# untitled.net
KiCad netlist of a schematic drawn in EAGLE
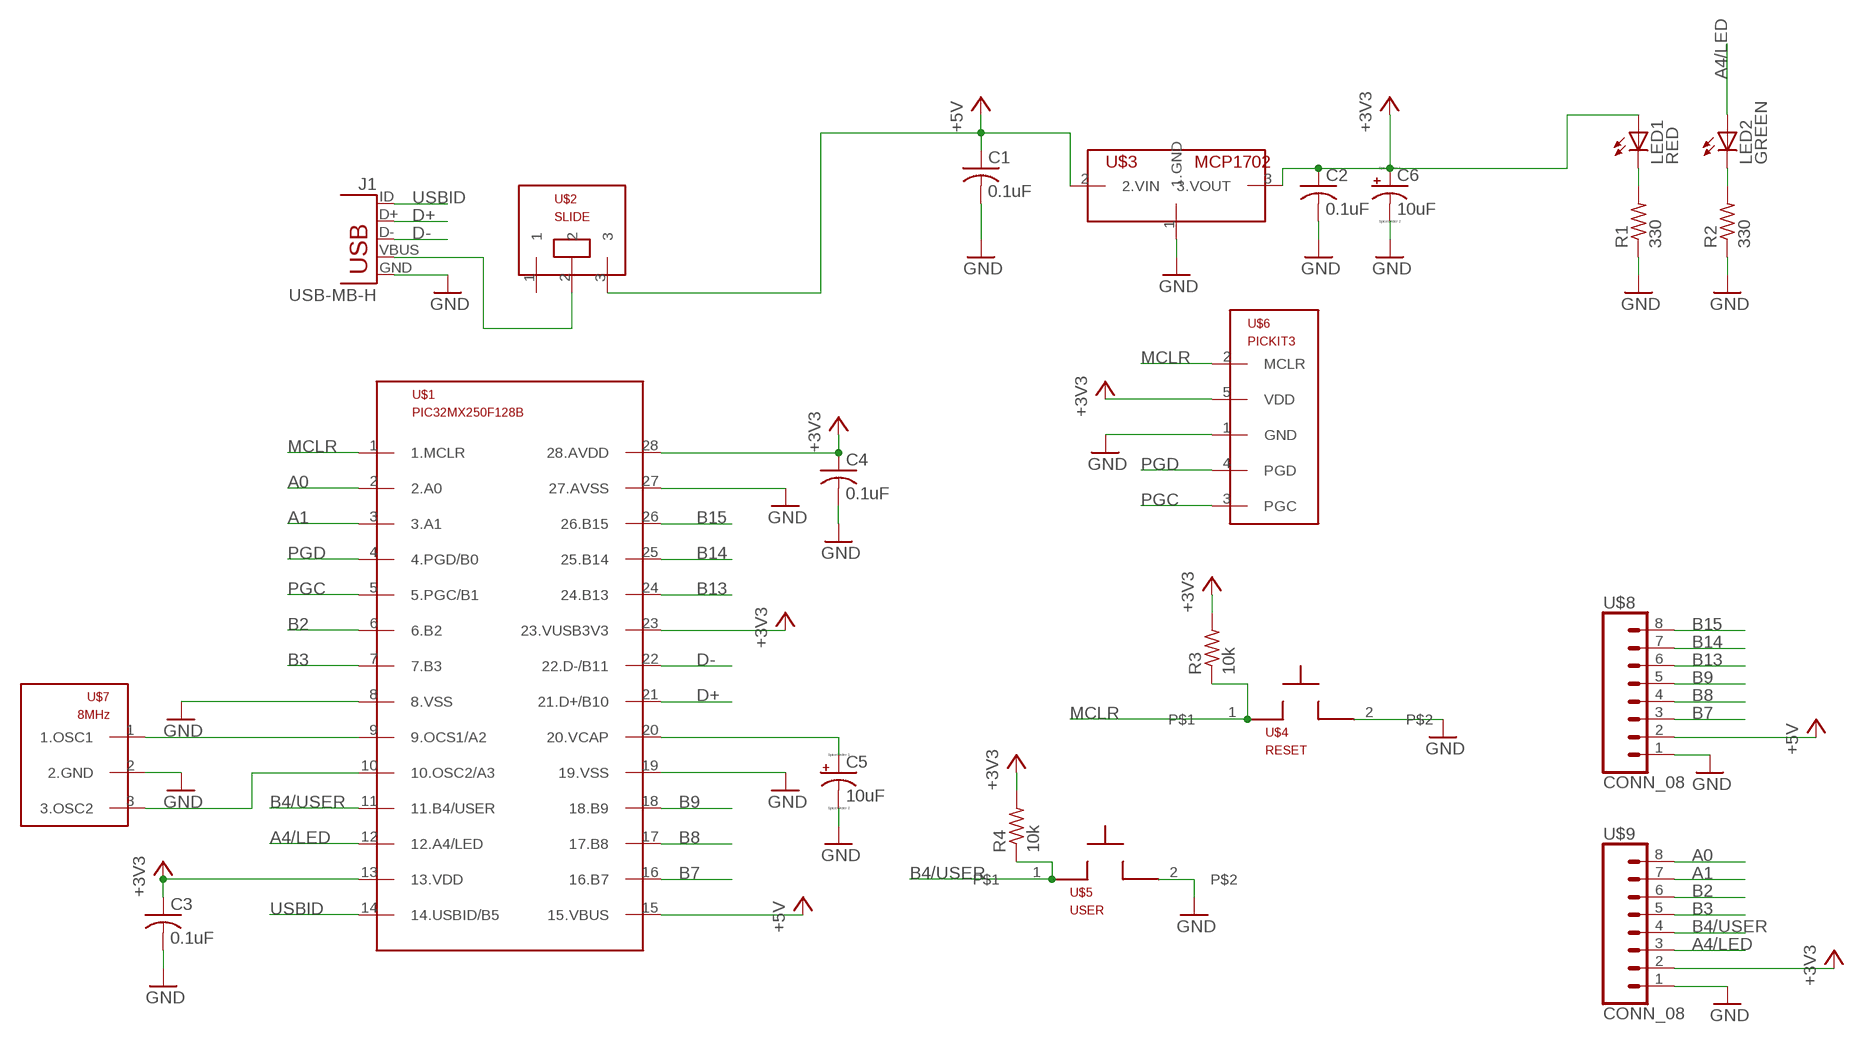
[diagram p0: schematic, sheet 1]

(export (version "E")
  (design (tool "Eeschema 10.0.6"))
  (components
    (comp (ref "C1")
      (value "0.1uF")
      (footprint "eagle-import:C025-025X050")
      (libsource (lib "eagle-import") (part "C-US025-025X050"))
    )
    (comp (ref "C2")
      (value "0.1uF")
      (footprint "eagle-import:C025-025X050")
      (libsource (lib "eagle-import") (part "C-US025-025X050"))
    )
    (comp (ref "C3")
      (value "0.1uF")
      (footprint "eagle-import:C025-025X050")
      (libsource (lib "eagle-import") (part "C-US025-025X050"))
    )
    (comp (ref "C4")
      (value "0.1uF")
      (footprint "eagle-import:C025-025X050")
      (libsource (lib "eagle-import") (part "C-US025-025X050"))
    )
    (comp (ref "C5")
      (value "10uF")
      (footprint "eagle-import:B45181B")
      (libsource (lib "eagle-import") (part "CPOL-USB45181B"))
    )
    (comp (ref "C6")
      (value "10uF")
      (footprint "eagle-import:B45181B")
      (libsource (lib "eagle-import") (part "CPOL-USB45181B"))
    )
    (comp (ref "J1")
      (value "USB-MB-H")
      (footprint "eagle-import:USB-MB-H")
      (libsource (lib "eagle-import") (part "USB-MB-H"))
    )
    (comp (ref "LED1")
      (value "RED")
      (footprint "eagle-import:LED3MM")
      (libsource (lib "eagle-import") (part "LED3MM"))
    )
    (comp (ref "LED2")
      (value "GREEN")
      (footprint "eagle-import:LED3MM")
      (libsource (lib "eagle-import") (part "LED3MM"))
    )
    (comp (ref "R1")
      (value "330")
      (footprint "eagle-import:0207_10")
      (libsource (lib "eagle-import") (part "R-US_0207/10"))
    )
    (comp (ref "R2")
      (value "330")
      (footprint "eagle-import:0207_10")
      (libsource (lib "eagle-import") (part "R-US_0207/10"))
    )
    (comp (ref "R3")
      (value "10k")
      (footprint "eagle-import:0207_10")
      (libsource (lib "eagle-import") (part "R-US_0207/10"))
    )
    (comp (ref "R4")
      (value "10k")
      (footprint "eagle-import:0207_10")
      (libsource (lib "eagle-import") (part "R-US_0207/10"))
    )
    (comp (ref "U$1")
      (value "PIC32MX250F128B")
      (footprint "eagle-import:DIL28-3")
      (libsource (lib "eagle-import") (part "PIC32MX250F128B"))
    )
    (comp (ref "U$2")
      (value "SLIDE")
      (footprint "eagle-import:SLIDE")
      (libsource (lib "eagle-import") (part "SLIDE"))
    )
    (comp (ref "U$3")
      (value "MCP1702")
      (footprint "eagle-import:TO92")
      (libsource (lib "eagle-import") (part "MCP1702"))
    )
    (comp (ref "U$4")
      (value "RESET")
      (footprint "eagle-import:PB")
      (libsource (lib "eagle-import") (part "PB"))
    )
    (comp (ref "U$5")
      (value "USER")
      (footprint "eagle-import:PB")
      (libsource (lib "eagle-import") (part "PB"))
    )
    (comp (ref "U$6")
      (value "PICKIT3")
      (footprint "eagle-import:1X05")
      (libsource (lib "eagle-import") (part "PICKIT3"))
    )
    (comp (ref "U$7")
      (value "8MHz")
      (footprint "eagle-import:OSC")
      (libsource (lib "eagle-import") (part "OCS"))
    )
    (comp (ref "U$8")
      (value "CONN_08")
      (footprint "eagle-import:1X08")
      (libsource (lib "eagle-import") (part "CONN_08"))
    )
    (comp (ref "U$9")
      (value "CONN_08")
      (footprint "eagle-import:1X08")
      (libsource (lib "eagle-import") (part "CONN_08"))
    )
  )
  (nets
    (net (code "1") (name "+3V3") (class "Default")
      (node (ref "C2") (pin "1") (pinfunction "1_1") (pintype "passive"))
      (node (ref "C3") (pin "1") (pinfunction "1_1") (pintype "passive"))
      (node (ref "C4") (pin "1") (pinfunction "1_1") (pintype "passive"))
      (node (ref "C6") (pin "+") (pinfunction "+_+") (pintype "passive"))
      (node (ref "LED1") (pin "A") (pinfunction "A_A") (pintype "passive"))
      (node (ref "R3") (pin "2") (pinfunction "2_2") (pintype "passive"))
      (node (ref "R4") (pin "2") (pinfunction "2_2") (pintype "passive"))
      (node (ref "U$1") (pin "13") (pinfunction "13.VDD_13") (pintype "bidirectional"))
      (node (ref "U$1") (pin "23") (pinfunction "23.VUSB3V3_23") (pintype "bidirectional"))
      (node (ref "U$1") (pin "28") (pinfunction "28.AVDD_28") (pintype "bidirectional"))
      (node (ref "U$3") (pin "3") (pinfunction "3.VOUT_3") (pintype "bidirectional"))
      (node (ref "U$6") (pin "5") (pinfunction "VDD_5") (pintype "bidirectional"))
      (node (ref "U$9") (pin "2") (pinfunction "2_2") (pintype "passive"))
    )
    (net (code "2") (name "+5V") (class "Default")
      (node (ref "C1") (pin "1") (pinfunction "1_1") (pintype "passive"))
      (node (ref "U$1") (pin "15") (pinfunction "15.VBUS_15") (pintype "bidirectional"))
      (node (ref "U$2") (pin "3") (pinfunction "3_3") (pintype "bidirectional"))
      (node (ref "U$3") (pin "2") (pinfunction "2.VIN_2") (pintype "bidirectional"))
      (node (ref "U$8") (pin "2") (pinfunction "2_2") (pintype "passive"))
    )
    (net (code "3") (name "/A0") (class "Default")
      (node (ref "U$1") (pin "2") (pinfunction "2.A0_2") (pintype "bidirectional"))
      (node (ref "U$9") (pin "8") (pinfunction "8_8") (pintype "passive"))
    )
    (net (code "4") (name "/A1") (class "Default")
      (node (ref "U$1") (pin "3") (pinfunction "3.A1_3") (pintype "bidirectional"))
      (node (ref "U$9") (pin "7") (pinfunction "7_7") (pintype "passive"))
    )
    (net (code "5") (name "/A4{slash}LED") (class "Default")
      (node (ref "LED2") (pin "A") (pinfunction "A_A") (pintype "passive"))
      (node (ref "U$1") (pin "12") (pinfunction "12.A4/LED_12") (pintype "bidirectional"))
      (node (ref "U$9") (pin "3") (pinfunction "3_3") (pintype "passive"))
    )
    (net (code "6") (name "/B2") (class "Default")
      (node (ref "U$1") (pin "6") (pinfunction "6.B2_6") (pintype "bidirectional"))
      (node (ref "U$9") (pin "6") (pinfunction "6_6") (pintype "passive"))
    )
    (net (code "7") (name "/B3") (class "Default")
      (node (ref "U$1") (pin "7") (pinfunction "7.B3_7") (pintype "bidirectional"))
      (node (ref "U$9") (pin "5") (pinfunction "5_5") (pintype "passive"))
    )
    (net (code "8") (name "/B4{slash}USER") (class "Default")
      (node (ref "R4") (pin "1") (pinfunction "1_1") (pintype "passive"))
      (node (ref "U$1") (pin "11") (pinfunction "11.B4/USER_11") (pintype "bidirectional"))
      (node (ref "U$5") (pin "1") (pinfunction "P$1_1") (pintype "bidirectional"))
      (node (ref "U$9") (pin "4") (pinfunction "4_4") (pintype "passive"))
    )
    (net (code "9") (name "/B7") (class "Default")
      (node (ref "U$1") (pin "16") (pinfunction "16.B7_16") (pintype "bidirectional"))
      (node (ref "U$8") (pin "3") (pinfunction "3_3") (pintype "passive"))
    )
    (net (code "10") (name "/B8") (class "Default")
      (node (ref "U$1") (pin "17") (pinfunction "17.B8_17") (pintype "bidirectional"))
      (node (ref "U$8") (pin "4") (pinfunction "4_4") (pintype "passive"))
    )
    (net (code "11") (name "/B9") (class "Default")
      (node (ref "U$1") (pin "18") (pinfunction "18.B9_18") (pintype "bidirectional"))
      (node (ref "U$8") (pin "5") (pinfunction "5_5") (pintype "passive"))
    )
    (net (code "12") (name "/B13") (class "Default")
      (node (ref "U$1") (pin "24") (pinfunction "24.B13_24") (pintype "bidirectional"))
      (node (ref "U$8") (pin "6") (pinfunction "6_6") (pintype "passive"))
    )
    (net (code "13") (name "/B14") (class "Default")
      (node (ref "U$1") (pin "25") (pinfunction "25.B14_25") (pintype "bidirectional"))
      (node (ref "U$8") (pin "7") (pinfunction "7_7") (pintype "passive"))
    )
    (net (code "14") (name "/B15") (class "Default")
      (node (ref "U$1") (pin "26") (pinfunction "26.B15_26") (pintype "bidirectional"))
      (node (ref "U$8") (pin "8") (pinfunction "8_8") (pintype "passive"))
    )
    (net (code "15") (name "/D+") (class "Default")
      (node (ref "J1") (pin "D+") (pinfunction "D+_D+") (pintype "bidirectional"))
      (node (ref "U$1") (pin "21") (pinfunction "21.D+/B10_21") (pintype "bidirectional"))
    )
    (net (code "16") (name "/D-") (class "Default")
      (node (ref "J1") (pin "D-") (pinfunction "D-_D-") (pintype "bidirectional"))
      (node (ref "U$1") (pin "22") (pinfunction "22.D-/B11_22") (pintype "bidirectional"))
    )
    (net (code "17") (name "/MCLR") (class "Default")
      (node (ref "R3") (pin "1") (pinfunction "1_1") (pintype "passive"))
      (node (ref "U$1") (pin "1") (pinfunction "1.MCLR_1") (pintype "bidirectional"))
      (node (ref "U$4") (pin "1") (pinfunction "P$1_1") (pintype "bidirectional"))
      (node (ref "U$6") (pin "2") (pinfunction "MCLR_2") (pintype "bidirectional"))
    )
    (net (code "18") (name "/PGC") (class "Default")
      (node (ref "U$1") (pin "5") (pinfunction "5.PGC/B1_5") (pintype "bidirectional"))
      (node (ref "U$6") (pin "3") (pinfunction "PGC_3") (pintype "bidirectional"))
    )
    (net (code "19") (name "/PGD") (class "Default")
      (node (ref "U$1") (pin "4") (pinfunction "4.PGD/B0_4") (pintype "bidirectional"))
      (node (ref "U$6") (pin "4") (pinfunction "PGD_4") (pintype "bidirectional"))
    )
    (net (code "20") (name "/USBID") (class "Default")
      (node (ref "J1") (pin "ID") (pinfunction "ID_ID") (pintype "bidirectional"))
      (node (ref "U$1") (pin "14") (pinfunction "14.USBID/B5_14") (pintype "bidirectional"))
    )
    (net (code "21") (name "GND") (class "Default")
      (node (ref "C1") (pin "2") (pinfunction "2_2") (pintype "passive"))
      (node (ref "C2") (pin "2") (pinfunction "2_2") (pintype "passive"))
      (node (ref "C3") (pin "2") (pinfunction "2_2") (pintype "passive"))
      (node (ref "C4") (pin "2") (pinfunction "2_2") (pintype "passive"))
      (node (ref "C5") (pin "-") (pinfunction "-_-") (pintype "passive"))
      (node (ref "C6") (pin "-") (pinfunction "-_-") (pintype "passive"))
      (node (ref "J1") (pin "GND") (pinfunction "GND_GND") (pintype "bidirectional"))
      (node (ref "R1") (pin "1") (pinfunction "1_1") (pintype "passive"))
      (node (ref "R2") (pin "1") (pinfunction "1_1") (pintype "passive"))
      (node (ref "U$1") (pin "19") (pinfunction "19.VSS_19") (pintype "bidirectional"))
      (node (ref "U$1") (pin "27") (pinfunction "27.AVSS_27") (pintype "bidirectional"))
      (node (ref "U$1") (pin "8") (pinfunction "8.VSS_8") (pintype "bidirectional"))
      (node (ref "U$3") (pin "1") (pinfunction "1.GND_1") (pintype "bidirectional"))
      (node (ref "U$4") (pin "2") (pinfunction "P$2_2") (pintype "bidirectional"))
      (node (ref "U$5") (pin "2") (pinfunction "P$2_2") (pintype "bidirectional"))
      (node (ref "U$6") (pin "1") (pinfunction "GND_1") (pintype "bidirectional"))
      (node (ref "U$7") (pin "2") (pinfunction "2.GND_2") (pintype "bidirectional"))
      (node (ref "U$8") (pin "1") (pinfunction "1_1") (pintype "passive"))
      (node (ref "U$9") (pin "1") (pinfunction "1_1") (pintype "passive"))
    )
    (net (code "22") (name "Net-(J1-PadVBUS)") (class "Default")
      (node (ref "J1") (pin "VBUS") (pinfunction "VBUS_VBUS") (pintype "bidirectional"))
      (node (ref "U$2") (pin "2") (pinfunction "2_2") (pintype "bidirectional"))
    )
    (net (code "23") (name "Net-(LED1-C)") (class "Default")
      (node (ref "LED1") (pin "K") (pinfunction "C_K") (pintype "passive"))
      (node (ref "R1") (pin "2") (pinfunction "2_2") (pintype "passive"))
    )
    (net (code "24") (name "Net-(LED2-C)") (class "Default")
      (node (ref "LED2") (pin "K") (pinfunction "C_K") (pintype "passive"))
      (node (ref "R2") (pin "2") (pinfunction "2_2") (pintype "passive"))
    )
    (net (code "25") (name "Net-(U$1-9.OCS1{slash}A2)") (class "Default")
      (node (ref "U$1") (pin "9") (pinfunction "9.OCS1/A2_9") (pintype "bidirectional"))
      (node (ref "U$7") (pin "1") (pinfunction "1.OSC1_1") (pintype "bidirectional"))
    )
    (net (code "26") (name "Net-(U$1-10.OSC2{slash}A3)") (class "Default")
      (node (ref "U$1") (pin "10") (pinfunction "10.OSC2/A3_10") (pintype "bidirectional"))
      (node (ref "U$7") (pin "3") (pinfunction "3.OSC2_3") (pintype "bidirectional"))
    )
    (net (code "27") (name "Net-(U$1-20.VCAP)") (class "Default")
      (node (ref "C5") (pin "+") (pinfunction "+_+") (pintype "passive"))
      (node (ref "U$1") (pin "20") (pinfunction "20.VCAP_20") (pintype "bidirectional"))
    )
    (net (code "28") (name "unconnected-(U$2-Pad1)") (class "Default")
      (node (ref "U$2") (pin "1") (pinfunction "1_1") (pintype "bidirectional"))
    )
  )
)
